# Blunderwood_LED_Driver.net
KiCad netlist of a schematic drawn in EAGLE
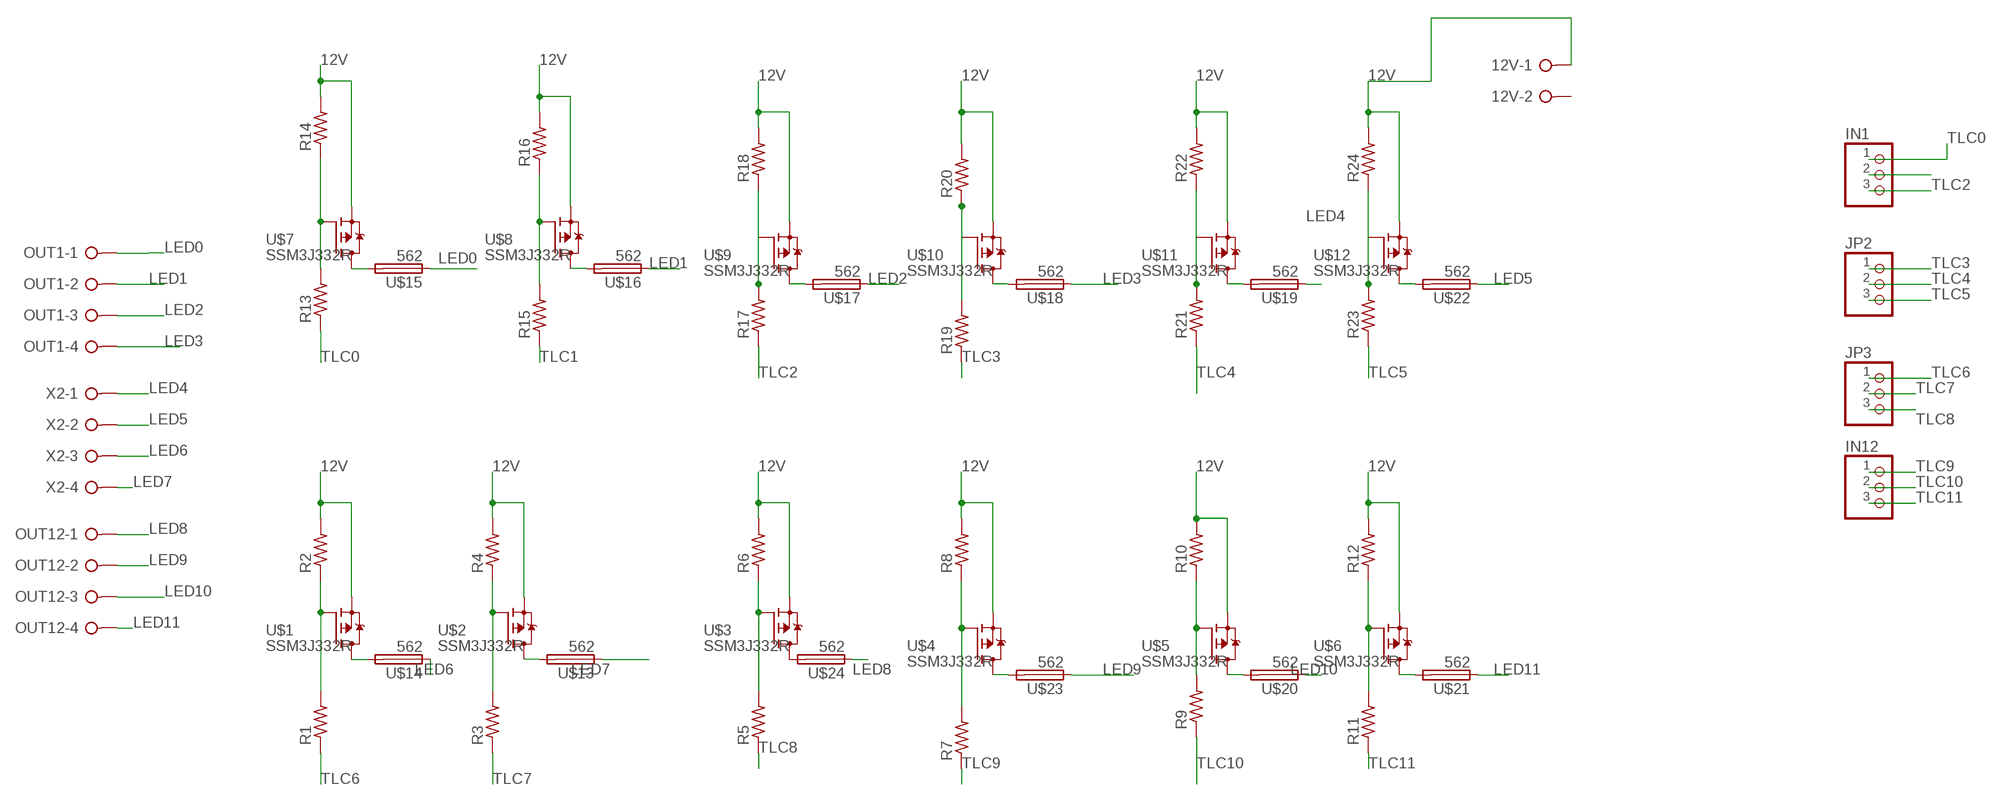
[diagram p0: schematic, sheet 1]

(export (version "E")
  (design (tool "Eeschema 10.0.6"))
  (components
    (comp (ref "12V")
      (value "W237-02P")
      (footprint "eagle-import:W237-132")
      (libsource (lib "eagle-import") (part "W237-02P"))
    )
    (comp (ref "IN1")
      (value "PINHD-1X3")
      (footprint "eagle-import:1X03")
      (libsource (lib "eagle-import") (part "PINHD-1X3"))
    )
    (comp (ref "IN12")
      (value "PINHD-1X3")
      (footprint "eagle-import:1X03")
      (libsource (lib "eagle-import") (part "PINHD-1X3"))
    )
    (comp (ref "JP2")
      (value "PINHD-1X3")
      (footprint "eagle-import:1X03")
      (libsource (lib "eagle-import") (part "PINHD-1X3"))
    )
    (comp (ref "JP3")
      (value "PINHD-1X3")
      (footprint "eagle-import:1X03")
      (libsource (lib "eagle-import") (part "PINHD-1X3"))
    )
    (comp (ref "OUT1")
      (value "W237-04P")
      (footprint "eagle-import:W237-4P")
      (libsource (lib "eagle-import") (part "W237-04P"))
    )
    (comp (ref "OUT12")
      (value "W237-04P")
      (footprint "eagle-import:W237-4P")
      (libsource (lib "eagle-import") (part "W237-04P"))
    )
    (comp (ref "R1")
      (value "R-US_R0805")
      (footprint "eagle-import:R0805")
      (libsource (lib "eagle-import") (part "R-US_R0805"))
    )
    (comp (ref "R2")
      (value "R-US_R0805")
      (footprint "eagle-import:R0805")
      (libsource (lib "eagle-import") (part "R-US_R0805"))
    )
    (comp (ref "R3")
      (value "R-US_R0805")
      (footprint "eagle-import:R0805")
      (libsource (lib "eagle-import") (part "R-US_R0805"))
    )
    (comp (ref "R4")
      (value "R-US_R0805")
      (footprint "eagle-import:R0805")
      (libsource (lib "eagle-import") (part "R-US_R0805"))
    )
    (comp (ref "R5")
      (value "R-US_R0805")
      (footprint "eagle-import:R0805")
      (libsource (lib "eagle-import") (part "R-US_R0805"))
    )
    (comp (ref "R6")
      (value "R-US_R0805")
      (footprint "eagle-import:R0805")
      (libsource (lib "eagle-import") (part "R-US_R0805"))
    )
    (comp (ref "R7")
      (value "R-US_R0805")
      (footprint "eagle-import:R0805")
      (libsource (lib "eagle-import") (part "R-US_R0805"))
    )
    (comp (ref "R8")
      (value "R-US_R0805")
      (footprint "eagle-import:R0805")
      (libsource (lib "eagle-import") (part "R-US_R0805"))
    )
    (comp (ref "R9")
      (value "R-US_R0805")
      (footprint "eagle-import:R0805")
      (libsource (lib "eagle-import") (part "R-US_R0805"))
    )
    (comp (ref "R10")
      (value "R-US_R0805")
      (footprint "eagle-import:R0805")
      (libsource (lib "eagle-import") (part "R-US_R0805"))
    )
    (comp (ref "R11")
      (value "R-US_R0805")
      (footprint "eagle-import:R0805")
      (libsource (lib "eagle-import") (part "R-US_R0805"))
    )
    (comp (ref "R12")
      (value "R-US_R0805")
      (footprint "eagle-import:R0805")
      (libsource (lib "eagle-import") (part "R-US_R0805"))
    )
    (comp (ref "R13")
      (value "R-US_R0805")
      (footprint "eagle-import:R0805")
      (libsource (lib "eagle-import") (part "R-US_R0805"))
    )
    (comp (ref "R14")
      (value "R-US_R0805")
      (footprint "eagle-import:R0805")
      (libsource (lib "eagle-import") (part "R-US_R0805"))
    )
    (comp (ref "R15")
      (value "R-US_R0805")
      (footprint "eagle-import:R0805")
      (libsource (lib "eagle-import") (part "R-US_R0805"))
    )
    (comp (ref "R16")
      (value "R-US_R0805")
      (footprint "eagle-import:R0805")
      (libsource (lib "eagle-import") (part "R-US_R0805"))
    )
    (comp (ref "R17")
      (value "R-US_R0805")
      (footprint "eagle-import:R0805")
      (libsource (lib "eagle-import") (part "R-US_R0805"))
    )
    (comp (ref "R18")
      (value "R-US_R0805")
      (footprint "eagle-import:R0805")
      (libsource (lib "eagle-import") (part "R-US_R0805"))
    )
    (comp (ref "R19")
      (value "R-US_R0805")
      (footprint "eagle-import:R0805")
      (libsource (lib "eagle-import") (part "R-US_R0805"))
    )
    (comp (ref "R20")
      (value "R-US_R0805")
      (footprint "eagle-import:R0805")
      (libsource (lib "eagle-import") (part "R-US_R0805"))
    )
    (comp (ref "R21")
      (value "R-US_R0805")
      (footprint "eagle-import:R0805")
      (libsource (lib "eagle-import") (part "R-US_R0805"))
    )
    (comp (ref "R22")
      (value "R-US_R0805")
      (footprint "eagle-import:R0805")
      (libsource (lib "eagle-import") (part "R-US_R0805"))
    )
    (comp (ref "R23")
      (value "R-US_R0805")
      (footprint "eagle-import:R0805")
      (libsource (lib "eagle-import") (part "R-US_R0805"))
    )
    (comp (ref "R24")
      (value "R-US_R0805")
      (footprint "eagle-import:R0805")
      (libsource (lib "eagle-import") (part "R-US_R0805"))
    )
    (comp (ref "U$1")
      (value "SSM3J332R")
      (footprint "eagle-import:SOT23")
      (libsource (lib "eagle-import") (part "SSM3J332R"))
    )
    (comp (ref "U$2")
      (value "SSM3J332R")
      (footprint "eagle-import:SOT23")
      (libsource (lib "eagle-import") (part "SSM3J332R"))
    )
    (comp (ref "U$3")
      (value "SSM3J332R")
      (footprint "eagle-import:SOT23")
      (libsource (lib "eagle-import") (part "SSM3J332R"))
    )
    (comp (ref "U$4")
      (value "SSM3J332R")
      (footprint "eagle-import:SOT23")
      (libsource (lib "eagle-import") (part "SSM3J332R"))
    )
    (comp (ref "U$5")
      (value "SSM3J332R")
      (footprint "eagle-import:SOT23")
      (libsource (lib "eagle-import") (part "SSM3J332R"))
    )
    (comp (ref "U$6")
      (value "SSM3J332R")
      (footprint "eagle-import:SOT23")
      (libsource (lib "eagle-import") (part "SSM3J332R"))
    )
    (comp (ref "U$7")
      (value "SSM3J332R")
      (footprint "eagle-import:SOT23")
      (libsource (lib "eagle-import") (part "SSM3J332R"))
    )
    (comp (ref "U$8")
      (value "SSM3J332R")
      (footprint "eagle-import:SOT23")
      (libsource (lib "eagle-import") (part "SSM3J332R"))
    )
    (comp (ref "U$9")
      (value "SSM3J332R")
      (footprint "eagle-import:SOT23")
      (libsource (lib "eagle-import") (part "SSM3J332R"))
    )
    (comp (ref "U$10")
      (value "SSM3J332R")
      (footprint "eagle-import:SOT23")
      (libsource (lib "eagle-import") (part "SSM3J332R"))
    )
    (comp (ref "U$11")
      (value "SSM3J332R")
      (footprint "eagle-import:SOT23")
      (libsource (lib "eagle-import") (part "SSM3J332R"))
    )
    (comp (ref "U$12")
      (value "SSM3J332R")
      (footprint "eagle-import:SOT23")
      (libsource (lib "eagle-import") (part "SSM3J332R"))
    )
    (comp (ref "U$13")
      (value "562")
      (footprint "eagle-import:564")
      (libsource (lib "eagle-import") (part "562"))
    )
    (comp (ref "U$14")
      (value "562")
      (footprint "eagle-import:564")
      (libsource (lib "eagle-import") (part "562"))
    )
    (comp (ref "U$15")
      (value "562")
      (footprint "eagle-import:564")
      (libsource (lib "eagle-import") (part "562"))
    )
    (comp (ref "U$16")
      (value "562")
      (footprint "eagle-import:564")
      (libsource (lib "eagle-import") (part "562"))
    )
    (comp (ref "U$17")
      (value "562")
      (footprint "eagle-import:564")
      (libsource (lib "eagle-import") (part "562"))
    )
    (comp (ref "U$18")
      (value "562")
      (footprint "eagle-import:564")
      (libsource (lib "eagle-import") (part "562"))
    )
    (comp (ref "U$19")
      (value "562")
      (footprint "eagle-import:564")
      (libsource (lib "eagle-import") (part "562"))
    )
    (comp (ref "U$20")
      (value "562")
      (footprint "eagle-import:564")
      (libsource (lib "eagle-import") (part "562"))
    )
    (comp (ref "U$21")
      (value "562")
      (footprint "eagle-import:564")
      (libsource (lib "eagle-import") (part "562"))
    )
    (comp (ref "U$22")
      (value "562")
      (footprint "eagle-import:564")
      (libsource (lib "eagle-import") (part "562"))
    )
    (comp (ref "U$23")
      (value "562")
      (footprint "eagle-import:564")
      (libsource (lib "eagle-import") (part "562"))
    )
    (comp (ref "U$24")
      (value "562")
      (footprint "eagle-import:564")
      (libsource (lib "eagle-import") (part "562"))
    )
    (comp (ref "X2")
      (value "W237-04P")
      (footprint "eagle-import:W237-4P")
      (libsource (lib "eagle-import") (part "W237-04P"))
    )
  )
  (nets
    (net (code "1") (name "/12V") (class "Default")
      (node (ref "12V") (pin "1") (pinfunction "KL_1") (pintype "passive"))
      (node (ref "R10") (pin "2") (pinfunction "2_2") (pintype "passive"))
      (node (ref "R12") (pin "2") (pinfunction "2_2") (pintype "passive"))
      (node (ref "R14") (pin "2") (pinfunction "2_2") (pintype "passive"))
      (node (ref "R16") (pin "2") (pinfunction "2_2") (pintype "passive"))
      (node (ref "R18") (pin "2") (pinfunction "2_2") (pintype "passive"))
      (node (ref "R2") (pin "2") (pinfunction "2_2") (pintype "passive"))
      (node (ref "R20") (pin "2") (pinfunction "2_2") (pintype "passive"))
      (node (ref "R22") (pin "2") (pinfunction "2_2") (pintype "passive"))
      (node (ref "R24") (pin "2") (pinfunction "2_2") (pintype "passive"))
      (node (ref "R4") (pin "2") (pinfunction "2_2") (pintype "passive"))
      (node (ref "R6") (pin "2") (pinfunction "2_2") (pintype "passive"))
      (node (ref "R8") (pin "2") (pinfunction "2_2") (pintype "passive"))
      (node (ref "U$1") (pin "2") (pinfunction "S_2") (pintype "passive"))
      (node (ref "U$10") (pin "2") (pinfunction "S_2") (pintype "passive"))
      (node (ref "U$11") (pin "2") (pinfunction "S_2") (pintype "passive"))
      (node (ref "U$12") (pin "2") (pinfunction "S_2") (pintype "passive"))
      (node (ref "U$2") (pin "2") (pinfunction "S_2") (pintype "passive"))
      (node (ref "U$3") (pin "2") (pinfunction "S_2") (pintype "passive"))
      (node (ref "U$4") (pin "2") (pinfunction "S_2") (pintype "passive"))
      (node (ref "U$5") (pin "2") (pinfunction "S_2") (pintype "passive"))
      (node (ref "U$6") (pin "2") (pinfunction "S_2") (pintype "passive"))
      (node (ref "U$7") (pin "2") (pinfunction "S_2") (pintype "passive"))
      (node (ref "U$8") (pin "2") (pinfunction "S_2") (pintype "passive"))
      (node (ref "U$9") (pin "2") (pinfunction "S_2") (pintype "passive"))
    )
    (net (code "2") (name "/LED0") (class "Default")
      (node (ref "OUT1") (pin "1") (pinfunction "KL_1") (pintype "passive"))
      (node (ref "U$15") (pin "P$3") (pinfunction "1_P$3") (pintype "passive"))
    )
    (net (code "3") (name "/LED1") (class "Default")
      (node (ref "OUT1") (pin "2") (pinfunction "KL_2") (pintype "passive"))
      (node (ref "U$16") (pin "P$3") (pinfunction "1_P$3") (pintype "passive"))
    )
    (net (code "4") (name "/LED2") (class "Default")
      (node (ref "OUT1") (pin "3") (pinfunction "KL_3") (pintype "passive"))
      (node (ref "U$17") (pin "P$3") (pinfunction "1_P$3") (pintype "passive"))
    )
    (net (code "5") (name "/LED3") (class "Default")
      (node (ref "OUT1") (pin "4") (pinfunction "KL_4") (pintype "passive"))
      (node (ref "U$18") (pin "P$3") (pinfunction "1_P$3") (pintype "passive"))
    )
    (net (code "6") (name "/LED4") (class "Default")
      (node (ref "U$19") (pin "P$3") (pinfunction "1_P$3") (pintype "passive"))
      (node (ref "X2") (pin "1") (pinfunction "KL_1") (pintype "passive"))
    )
    (net (code "7") (name "/LED5") (class "Default")
      (node (ref "U$22") (pin "P$3") (pinfunction "1_P$3") (pintype "passive"))
      (node (ref "X2") (pin "2") (pinfunction "KL_2") (pintype "passive"))
    )
    (net (code "8") (name "/LED6") (class "Default")
      (node (ref "U$14") (pin "P$3") (pinfunction "1_P$3") (pintype "passive"))
      (node (ref "X2") (pin "3") (pinfunction "KL_3") (pintype "passive"))
    )
    (net (code "9") (name "/LED7") (class "Default")
      (node (ref "U$13") (pin "P$3") (pinfunction "1_P$3") (pintype "passive"))
      (node (ref "X2") (pin "4") (pinfunction "KL_4") (pintype "passive"))
    )
    (net (code "10") (name "/LED8") (class "Default")
      (node (ref "OUT12") (pin "1") (pinfunction "KL_1") (pintype "passive"))
      (node (ref "U$24") (pin "P$3") (pinfunction "1_P$3") (pintype "passive"))
    )
    (net (code "11") (name "/LED9") (class "Default")
      (node (ref "OUT12") (pin "2") (pinfunction "KL_2") (pintype "passive"))
      (node (ref "U$23") (pin "P$3") (pinfunction "1_P$3") (pintype "passive"))
    )
    (net (code "12") (name "/LED10") (class "Default")
      (node (ref "OUT12") (pin "3") (pinfunction "KL_3") (pintype "passive"))
      (node (ref "U$20") (pin "P$3") (pinfunction "1_P$3") (pintype "passive"))
    )
    (net (code "13") (name "/LED11") (class "Default")
      (node (ref "OUT12") (pin "4") (pinfunction "KL_4") (pintype "passive"))
      (node (ref "U$21") (pin "P$3") (pinfunction "1_P$3") (pintype "passive"))
    )
    (net (code "14") (name "/TLC0") (class "Default")
      (node (ref "IN1") (pin "1") (pinfunction "1_1") (pintype "passive"))
      (node (ref "R13") (pin "1") (pinfunction "1_1") (pintype "passive"))
    )
    (net (code "15") (name "/TLC1") (class "Default")
      (node (ref "IN1") (pin "2") (pinfunction "2_2") (pintype "passive"))
      (node (ref "R15") (pin "1") (pinfunction "1_1") (pintype "passive"))
    )
    (net (code "16") (name "/TLC2") (class "Default")
      (node (ref "IN1") (pin "3") (pinfunction "3_3") (pintype "passive"))
      (node (ref "R17") (pin "1") (pinfunction "1_1") (pintype "passive"))
    )
    (net (code "17") (name "/TLC3") (class "Default")
      (node (ref "JP2") (pin "1") (pinfunction "1_1") (pintype "passive"))
      (node (ref "R19") (pin "1") (pinfunction "1_1") (pintype "passive"))
    )
    (net (code "18") (name "/TLC4") (class "Default")
      (node (ref "JP2") (pin "2") (pinfunction "2_2") (pintype "passive"))
      (node (ref "R21") (pin "1") (pinfunction "1_1") (pintype "passive"))
    )
    (net (code "19") (name "/TLC5") (class "Default")
      (node (ref "JP2") (pin "3") (pinfunction "3_3") (pintype "passive"))
      (node (ref "R23") (pin "1") (pinfunction "1_1") (pintype "passive"))
    )
    (net (code "20") (name "/TLC6") (class "Default")
      (node (ref "JP3") (pin "1") (pinfunction "1_1") (pintype "passive"))
      (node (ref "R1") (pin "1") (pinfunction "1_1") (pintype "passive"))
    )
    (net (code "21") (name "/TLC7") (class "Default")
      (node (ref "JP3") (pin "2") (pinfunction "2_2") (pintype "passive"))
      (node (ref "R3") (pin "1") (pinfunction "1_1") (pintype "passive"))
    )
    (net (code "22") (name "/TLC8") (class "Default")
      (node (ref "JP3") (pin "3") (pinfunction "3_3") (pintype "passive"))
      (node (ref "R5") (pin "1") (pinfunction "1_1") (pintype "passive"))
    )
    (net (code "23") (name "/TLC9") (class "Default")
      (node (ref "IN12") (pin "1") (pinfunction "1_1") (pintype "passive"))
      (node (ref "R7") (pin "1") (pinfunction "1_1") (pintype "passive"))
    )
    (net (code "24") (name "/TLC10") (class "Default")
      (node (ref "IN12") (pin "2") (pinfunction "2_2") (pintype "passive"))
      (node (ref "R9") (pin "1") (pinfunction "1_1") (pintype "passive"))
    )
    (net (code "25") (name "/TLC11") (class "Default")
      (node (ref "IN12") (pin "3") (pinfunction "3_3") (pintype "passive"))
      (node (ref "R11") (pin "1") (pinfunction "1_1") (pintype "passive"))
    )
    (net (code "26") (name "Net-(U$1-D)") (class "Default")
      (node (ref "U$1") (pin "3") (pinfunction "D_3") (pintype "passive"))
      (node (ref "U$14") (pin "P$4") (pinfunction "2_P$4") (pintype "passive"))
    )
    (net (code "27") (name "Net-(U$1-G)") (class "Default")
      (node (ref "R1") (pin "2") (pinfunction "2_2") (pintype "passive"))
      (node (ref "R2") (pin "1") (pinfunction "1_1") (pintype "passive"))
      (node (ref "U$1") (pin "1") (pinfunction "G_1") (pintype "passive"))
    )
    (net (code "28") (name "Net-(U$2-G)") (class "Default")
      (node (ref "R3") (pin "2") (pinfunction "2_2") (pintype "passive"))
      (node (ref "R4") (pin "1") (pinfunction "1_1") (pintype "passive"))
      (node (ref "U$2") (pin "1") (pinfunction "G_1") (pintype "passive"))
    )
    (net (code "29") (name "Net-(U$3-G)") (class "Default")
      (node (ref "R5") (pin "2") (pinfunction "2_2") (pintype "passive"))
      (node (ref "R6") (pin "1") (pinfunction "1_1") (pintype "passive"))
      (node (ref "U$3") (pin "1") (pinfunction "G_1") (pintype "passive"))
    )
    (net (code "30") (name "Net-(U$4-G)") (class "Default")
      (node (ref "R7") (pin "2") (pinfunction "2_2") (pintype "passive"))
      (node (ref "R8") (pin "1") (pinfunction "1_1") (pintype "passive"))
      (node (ref "U$4") (pin "1") (pinfunction "G_1") (pintype "passive"))
    )
    (net (code "31") (name "Net-(U$5-G)") (class "Default")
      (node (ref "R10") (pin "1") (pinfunction "1_1") (pintype "passive"))
      (node (ref "R9") (pin "2") (pinfunction "2_2") (pintype "passive"))
      (node (ref "U$5") (pin "1") (pinfunction "G_1") (pintype "passive"))
    )
    (net (code "32") (name "Net-(U$6-G)") (class "Default")
      (node (ref "R11") (pin "2") (pinfunction "2_2") (pintype "passive"))
      (node (ref "R12") (pin "1") (pinfunction "1_1") (pintype "passive"))
      (node (ref "U$6") (pin "1") (pinfunction "G_1") (pintype "passive"))
    )
    (net (code "33") (name "Net-(U$7-G)") (class "Default")
      (node (ref "R13") (pin "2") (pinfunction "2_2") (pintype "passive"))
      (node (ref "R14") (pin "1") (pinfunction "1_1") (pintype "passive"))
      (node (ref "U$7") (pin "1") (pinfunction "G_1") (pintype "passive"))
    )
    (net (code "34") (name "Net-(U$8-G)") (class "Default")
      (node (ref "R15") (pin "2") (pinfunction "2_2") (pintype "passive"))
      (node (ref "R16") (pin "1") (pinfunction "1_1") (pintype "passive"))
      (node (ref "U$8") (pin "1") (pinfunction "G_1") (pintype "passive"))
    )
    (net (code "35") (name "Net-(U$9-G)") (class "Default")
      (node (ref "R17") (pin "2") (pinfunction "2_2") (pintype "passive"))
      (node (ref "R18") (pin "1") (pinfunction "1_1") (pintype "passive"))
      (node (ref "U$9") (pin "1") (pinfunction "G_1") (pintype "passive"))
    )
    (net (code "36") (name "Net-(U$10-D)") (class "Default")
      (node (ref "U$10") (pin "3") (pinfunction "D_3") (pintype "passive"))
      (node (ref "U$18") (pin "P$4") (pinfunction "2_P$4") (pintype "passive"))
    )
    (net (code "37") (name "Net-(U$10-G)") (class "Default")
      (node (ref "R19") (pin "2") (pinfunction "2_2") (pintype "passive"))
      (node (ref "R20") (pin "1") (pinfunction "1_1") (pintype "passive"))
      (node (ref "U$10") (pin "1") (pinfunction "G_1") (pintype "passive"))
    )
    (net (code "38") (name "Net-(U$11-D)") (class "Default")
      (node (ref "U$11") (pin "3") (pinfunction "D_3") (pintype "passive"))
      (node (ref "U$19") (pin "P$4") (pinfunction "2_P$4") (pintype "passive"))
    )
    (net (code "39") (name "Net-(U$11-G)") (class "Default")
      (node (ref "R21") (pin "2") (pinfunction "2_2") (pintype "passive"))
      (node (ref "R22") (pin "1") (pinfunction "1_1") (pintype "passive"))
      (node (ref "U$11") (pin "1") (pinfunction "G_1") (pintype "passive"))
    )
    (net (code "40") (name "Net-(U$12-D)") (class "Default")
      (node (ref "U$12") (pin "3") (pinfunction "D_3") (pintype "passive"))
      (node (ref "U$22") (pin "P$4") (pinfunction "2_P$4") (pintype "passive"))
    )
    (net (code "41") (name "Net-(U$12-G)") (class "Default")
      (node (ref "R23") (pin "2") (pinfunction "2_2") (pintype "passive"))
      (node (ref "R24") (pin "1") (pinfunction "1_1") (pintype "passive"))
      (node (ref "U$12") (pin "1") (pinfunction "G_1") (pintype "passive"))
    )
    (net (code "42") (name "Net-(U$13-2)") (class "Default")
      (node (ref "U$13") (pin "P$4") (pinfunction "2_P$4") (pintype "passive"))
      (node (ref "U$2") (pin "3") (pinfunction "D_3") (pintype "passive"))
    )
    (net (code "43") (name "Net-(U$15-2)") (class "Default")
      (node (ref "U$15") (pin "P$4") (pinfunction "2_P$4") (pintype "passive"))
      (node (ref "U$7") (pin "3") (pinfunction "D_3") (pintype "passive"))
    )
    (net (code "44") (name "Net-(U$16-2)") (class "Default")
      (node (ref "U$16") (pin "P$4") (pinfunction "2_P$4") (pintype "passive"))
      (node (ref "U$8") (pin "3") (pinfunction "D_3") (pintype "passive"))
    )
    (net (code "45") (name "Net-(U$17-2)") (class "Default")
      (node (ref "U$17") (pin "P$4") (pinfunction "2_P$4") (pintype "passive"))
      (node (ref "U$9") (pin "3") (pinfunction "D_3") (pintype "passive"))
    )
    (net (code "46") (name "Net-(U$20-2)") (class "Default")
      (node (ref "U$20") (pin "P$4") (pinfunction "2_P$4") (pintype "passive"))
      (node (ref "U$5") (pin "3") (pinfunction "D_3") (pintype "passive"))
    )
    (net (code "47") (name "Net-(U$21-2)") (class "Default")
      (node (ref "U$21") (pin "P$4") (pinfunction "2_P$4") (pintype "passive"))
      (node (ref "U$6") (pin "3") (pinfunction "D_3") (pintype "passive"))
    )
    (net (code "48") (name "Net-(U$23-2)") (class "Default")
      (node (ref "U$23") (pin "P$4") (pinfunction "2_P$4") (pintype "passive"))
      (node (ref "U$4") (pin "3") (pinfunction "D_3") (pintype "passive"))
    )
    (net (code "49") (name "Net-(U$24-2)") (class "Default")
      (node (ref "U$24") (pin "P$4") (pinfunction "2_P$4") (pintype "passive"))
      (node (ref "U$3") (pin "3") (pinfunction "D_3") (pintype "passive"))
    )
    (net (code "50") (name "unconnected-(12VB-KL-Pad2)") (class "Default")
      (node (ref "12V") (pin "2") (pinfunction "KL_2") (pintype "passive"))
    )
  )
)
